# 12V-to-5V-Converter.net
KiCad netlist of a schematic drawn in EAGLE
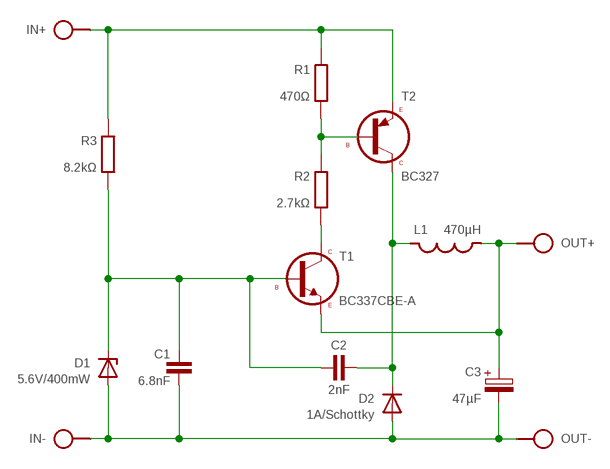
[diagram p0: schematic, sheet 1]

(export (version "E")
  (design (tool "Eeschema 10.0.6"))
  (components
    (comp (ref "C1")
      (value "6.8nF")
      (footprint "eagle-import:C025-050X050")
      (libsource (lib "eagle-import") (part "C025-050X050"))
    )
    (comp (ref "C2")
      (value "2nF")
      (footprint "eagle-import:C050-020X044")
      (libsource (lib "eagle-import") (part "C-H050-020X044"))
    )
    (comp (ref "C3")
      (value "47µF")
      (footprint "eagle-import:E2,5-5_V")
      (libsource (lib "eagle-import") (part "CPOLE2,5-5/V"))
    )
    (comp (ref "D1")
      (value "5.6V/400mW")
      (footprint "eagle-import:DO34Z10V")
      (libsource (lib "eagle-import") (part "Z-DIODE34Z10V"))
    )
    (comp (ref "D2")
      (value "1A/Schottky")
      (footprint "eagle-import:DO35-10")
      (libsource (lib "eagle-import") (part "DIODE35-10"))
    )
    (comp (ref "IN")
      (value "SPAD+-+-")
      (footprint "eagle-import:SPAD+-")
      (libsource (lib "eagle-import") (part "SPAD+-+-"))
    )
    (comp (ref "L1")
      (value "470µH")
      (footprint "eagle-import:ED16")
      (libsource (lib "eagle-import") (part "L-H-SHORT-03/10-X"))
    )
    (comp (ref "OUT")
      (value "SPAD+--+")
      (footprint "eagle-import:SPAD-+")
      (libsource (lib "eagle-import") (part "SPAD+--+"))
    )
    (comp (ref "R1")
      (value "470Ω")
      (footprint "eagle-import:0204_10-V")
      (libsource (lib "eagle-import") (part "R0204/10-V"))
    )
    (comp (ref "R2")
      (value "2.7kΩ")
      (footprint "eagle-import:0204_10-V")
      (libsource (lib "eagle-import") (part "R0204/10-V"))
    )
    (comp (ref "R3")
      (value "8.2kΩ")
      (footprint "eagle-import:0204_10-V")
      (libsource (lib "eagle-import") (part "R0204/10-V"))
    )
    (comp (ref "T1")
      (value "BC337CBE-A")
      (footprint "eagle-import:TO92-CBE-A")
      (libsource (lib "eagle-import") (part "BC337CBE-A"))
    )
    (comp (ref "T2")
      (value "BC327")
      (footprint "eagle-import:TO92")
      (libsource (lib "eagle-import") (part "BC327"))
    )
  )
  (nets
    (net (code "1") (name "Net-(INA-P$1)") (class "Default")
      (node (ref "IN") (pin "2") (pinfunction "P$1_2") (pintype "passive"))
      (node (ref "R1") (pin "1") (pinfunction "2_1") (pintype "passive"))
      (node (ref "R3") (pin "1") (pinfunction "2_1") (pintype "passive"))
      (node (ref "T2") (pin "3") (pinfunction "E_3") (pintype "passive"))
    )
    (net (code "2") (name "Net-(INB-P$1)") (class "Default")
      (node (ref "C1") (pin "2") (pinfunction "2_2") (pintype "passive"))
      (node (ref "C3") (pin "-") (pinfunction "-_-") (pintype "passive"))
      (node (ref "D1") (pin "A") (pinfunction "A_A") (pintype "passive"))
      (node (ref "D2") (pin "A") (pinfunction "A_A") (pintype "passive"))
      (node (ref "IN") (pin "1") (pinfunction "P$1_1") (pintype "passive"))
      (node (ref "OUT") (pin "1") (pinfunction "P$1_1") (pintype "passive"))
    )
    (net (code "3") (name "Net-(OUTA-P$1)") (class "Default")
      (node (ref "C3") (pin "+") (pinfunction "+_+") (pintype "passive"))
      (node (ref "L1") (pin "1") (pinfunction "1_1") (pintype "passive"))
      (node (ref "OUT") (pin "2") (pinfunction "P$1_2") (pintype "passive"))
      (node (ref "T1") (pin "3") (pinfunction "E_3") (pintype "passive"))
    )
    (net (code "4") (name "Net-(R1-1)") (class "Default")
      (node (ref "R1") (pin "2") (pinfunction "1_2") (pintype "passive"))
      (node (ref "R2") (pin "1") (pinfunction "2_1") (pintype "passive"))
      (node (ref "T2") (pin "2") (pinfunction "B_2") (pintype "passive"))
    )
    (net (code "5") (name "Net-(R2-1)") (class "Default")
      (node (ref "R2") (pin "2") (pinfunction "1_2") (pintype "passive"))
      (node (ref "T1") (pin "1") (pinfunction "C_1") (pintype "passive"))
    )
    (net (code "6") (name "Net-(R3-1)") (class "Default")
      (node (ref "C1") (pin "1") (pinfunction "1_1") (pintype "passive"))
      (node (ref "C2") (pin "1") (pinfunction "1_1") (pintype "passive"))
      (node (ref "D1") (pin "C") (pinfunction "C_C") (pintype "passive"))
      (node (ref "R3") (pin "2") (pinfunction "1_2") (pintype "passive"))
      (node (ref "T1") (pin "2") (pinfunction "B_2") (pintype "passive"))
    )
    (net (code "7") (name "Net-(T2-C)") (class "Default")
      (node (ref "C2") (pin "2") (pinfunction "2_2") (pintype "passive"))
      (node (ref "D2") (pin "C") (pinfunction "C_C") (pintype "passive"))
      (node (ref "L1") (pin "2") (pinfunction "2_2") (pintype "passive"))
      (node (ref "T2") (pin "1") (pinfunction "C_1") (pintype "passive"))
    )
  )
)
